# MEGA2560_Rev3e.net
KiCad netlist of a schematic drawn in EAGLE
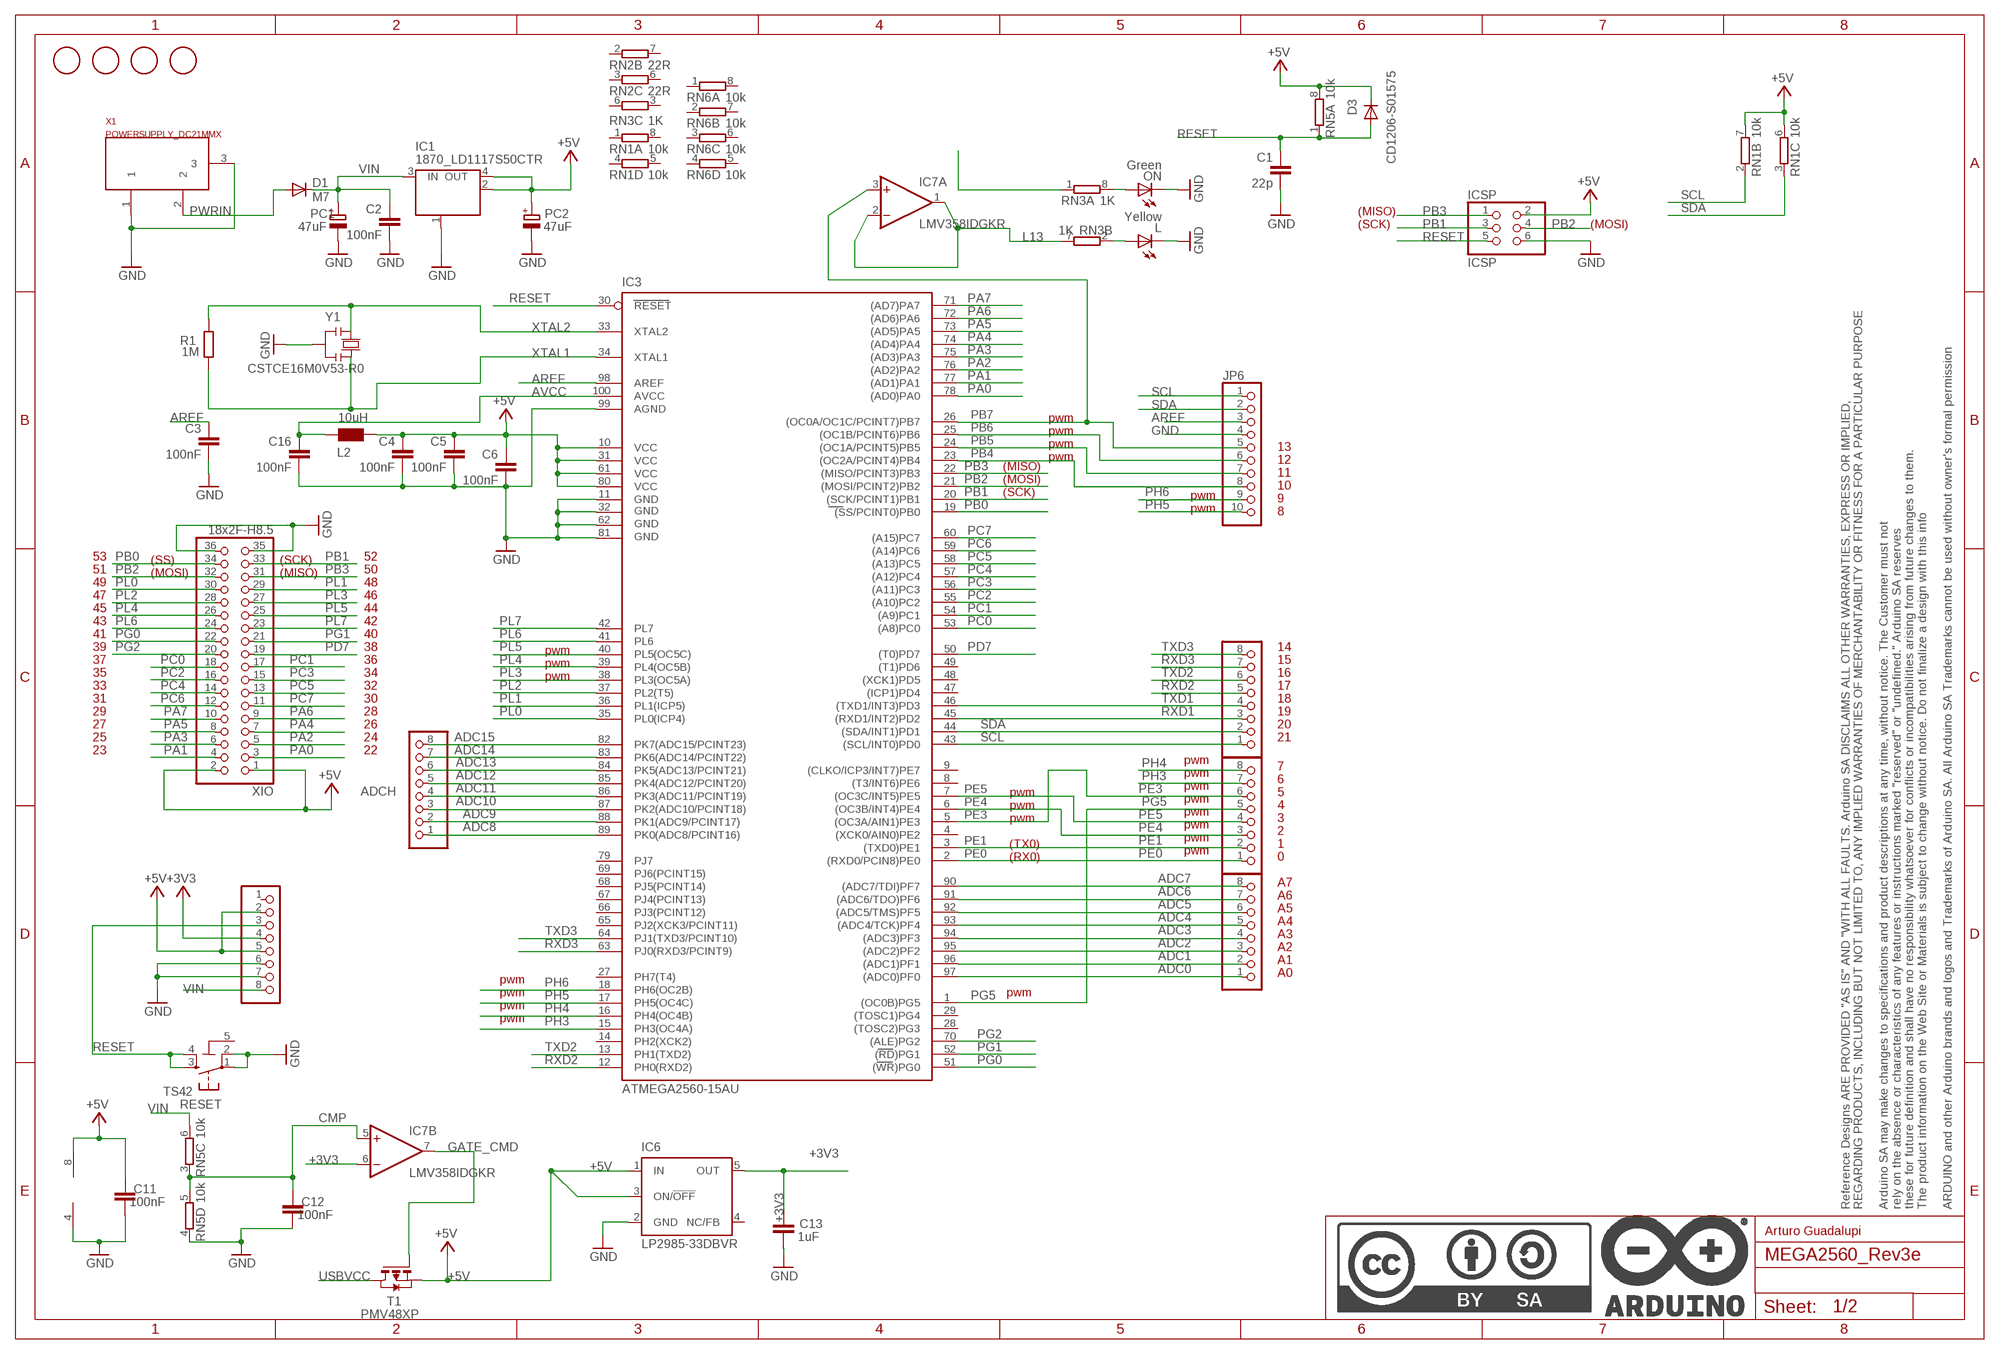
[diagram p0: schematic, sheet 1]
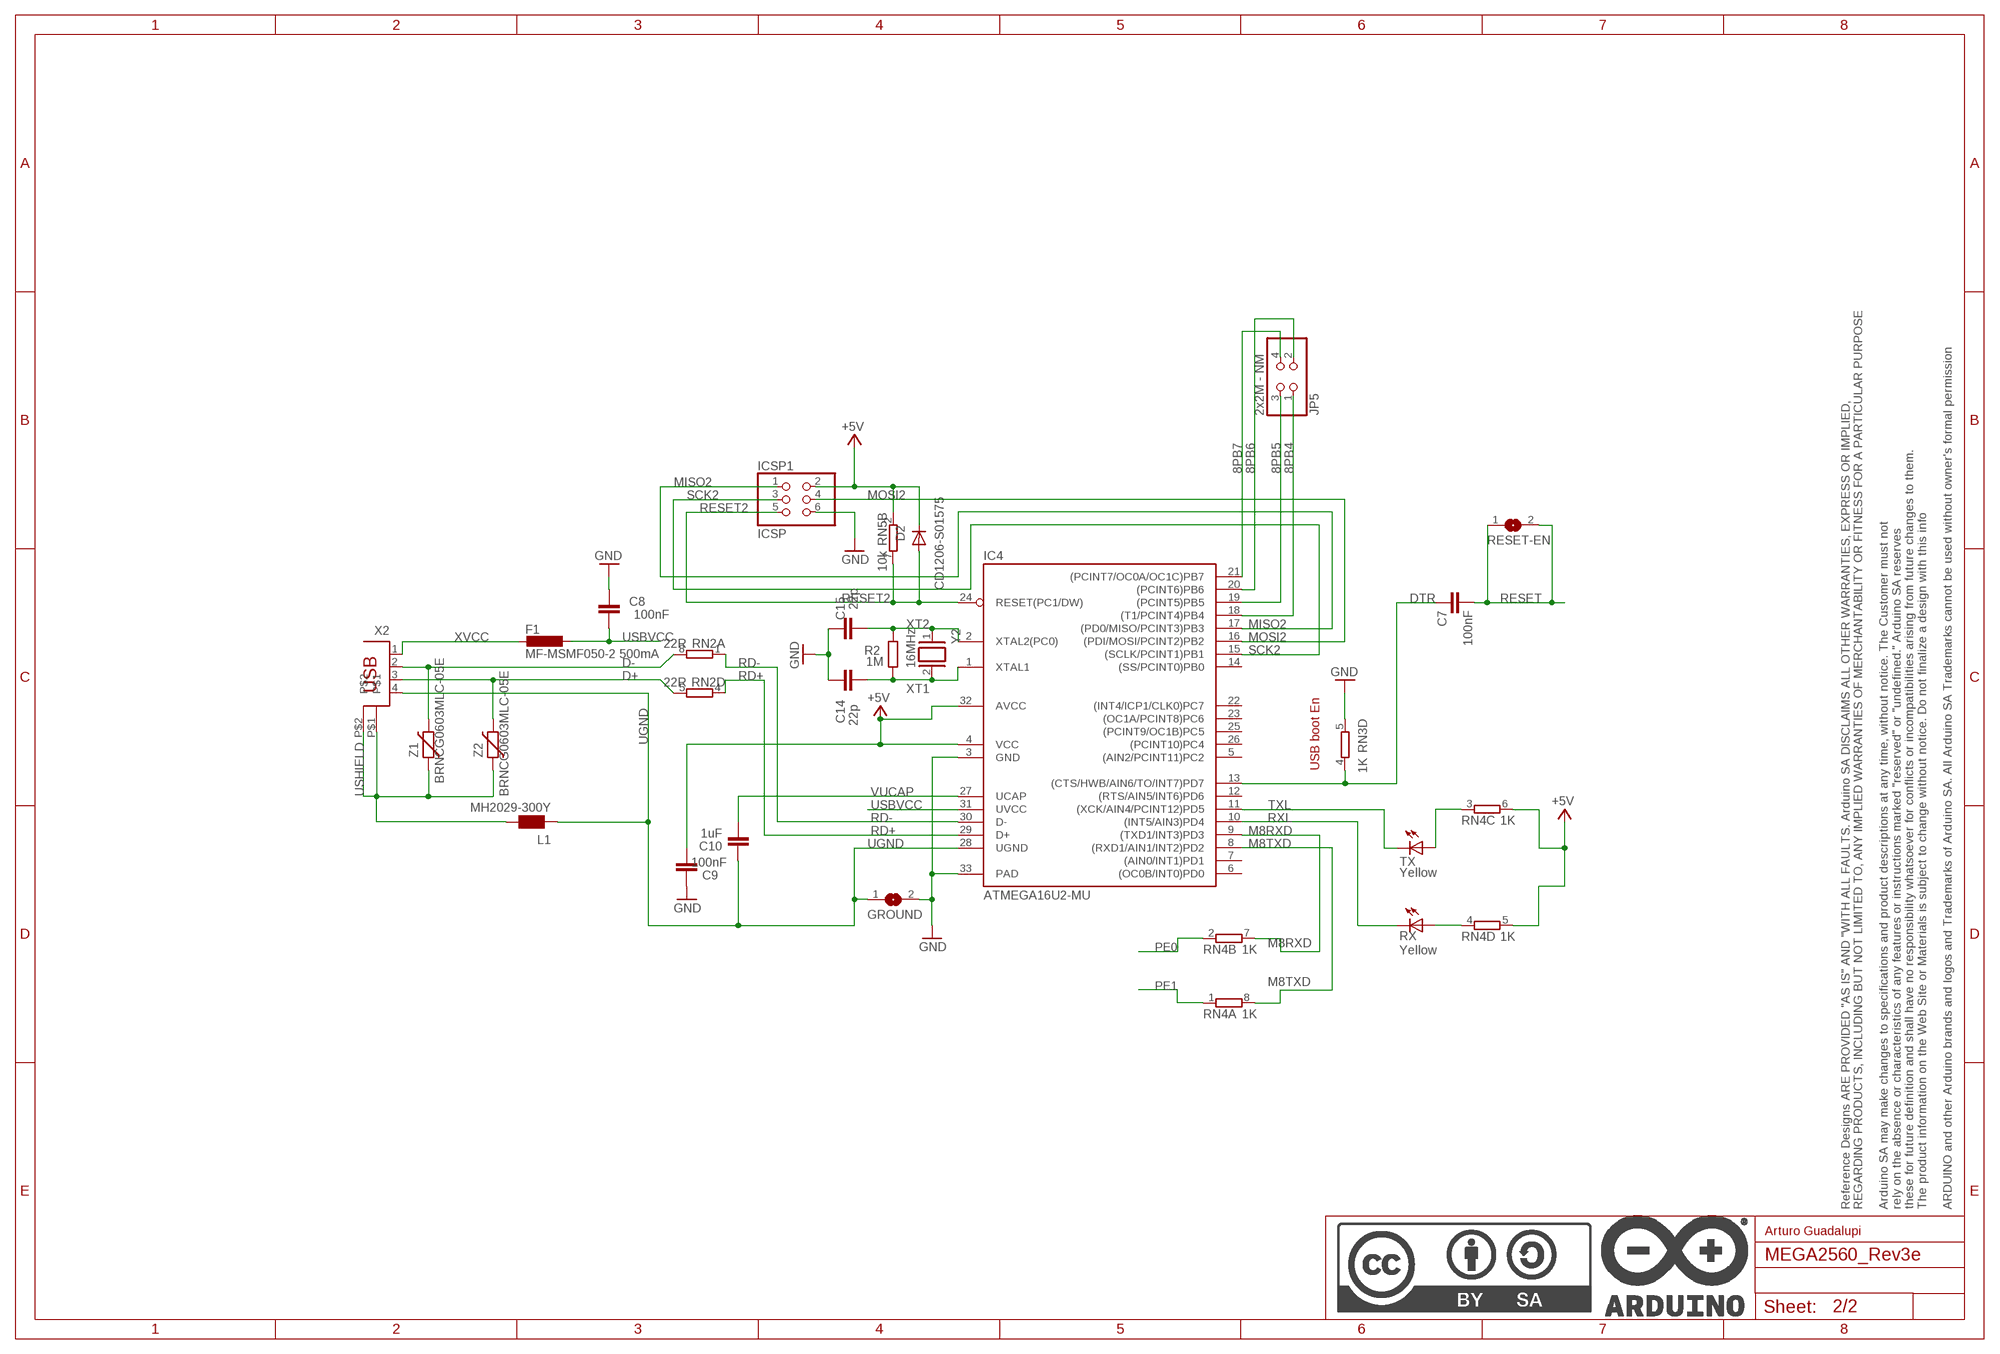
[diagram p1: schematic, sheet 2]

(export (version "E")
  (design (tool "Eeschema 10.0.6"))
  (components
    (comp (ref "C7")
      (value "100nF")
      (footprint "eagle-import:C0603-ROUND")
      (fields (field (name "PART_NUMBER") "cl10b104kbnc"))
      (libsource (lib "eagle-import") (part "0015_100NF_0603"))
    )
    (comp (ref "C8")
      (value "100nF")
      (footprint "eagle-import:C0603-ROUND")
      (fields (field (name "PART_NUMBER") "cl10b104kbnc"))
      (libsource (lib "eagle-import") (part "0015_100NF_0603"))
    )
    (comp (ref "C9")
      (value "100nF")
      (footprint "eagle-import:C0603-ROUND")
      (fields (field (name "PART_NUMBER") "cl10b104kbnc"))
      (libsource (lib "eagle-import") (part "0015_100NF_0603"))
    )
    (comp (ref "C10")
      (value "1uF")
      (footprint "eagle-import:C0603-ROUND")
      (fields (field (name "PART_NUMBER") "1uF_0603/GRM188R61E105KA12D"))
      (libsource (lib "eagle-import") (part "0006_1UF_0603/GRM188R61E105KA12D"))
    )
    (comp (ref "C14")
      (value "22p")
      (footprint "eagle-import:C0603-ROUND")
      (fields (field (name "PART_NUMBER") "22pF_0603"))
      (libsource (lib "eagle-import") (part "0014_22PF_0603"))
    )
    (comp (ref "C15")
      (value "22p")
      (footprint "eagle-import:C0603-ROUND")
      (fields (field (name "PART_NUMBER") "22pF_0603"))
      (libsource (lib "eagle-import") (part "0014_22PF_0603"))
    )
    (comp (ref "D2")
      (value "CD1206-S01575")
      (footprint "eagle-import:MINIMELF")
      (libsource (lib "eagle-import") (part "0012_CD1206-S01575"))
    )
    (comp (ref "F1")
      (value "MF-MSMF050-2 500mA")
      (footprint "eagle-import:L1812")
      (fields (field (name "PART_NUMBER") "MF-MSMF050-2"))
      (libsource (lib "eagle-import") (part "0002_MF-MSMF050-2"))
    )
    (comp (ref "GROUND")
      (value "SJ")
      (footprint "eagle-import:SJ")
      (libsource (lib "eagle-import") (part "SJ"))
    )
    (comp (ref "IC4")
      (value "ATMEGA16U2-MU")
      (footprint "eagle-import:MLF32")
      (fields (field (name "PART_NUMBER") "ATMEGA16U2-MUR"))
      (libsource (lib "eagle-import") (part "0007_ATMEGA16U2-MUR"))
    )
    (comp (ref "ICSP1")
      (value "ICSP")
      (footprint "eagle-import:2X03")
      (fields (field (name "PART_NUMBER") "PH254-203DF118A00V"))
      (libsource (lib "eagle-import") (part "0114_PH254-203DF118A00V"))
    )
    (comp (ref "JP5")
      (value "2x2M - NM")
      (footprint "eagle-import:2X02")
      (libsource (lib "eagle-import") (part "PINHD-2X2"))
    )
    (comp (ref "L1")
      (value "MH2029-300Y")
      (footprint "eagle-import:0805")
      (fields (field (name "PART_NUMBER") "BLM21PG300SN1D_/_MH2029-300Y"))
      (libsource (lib "eagle-import") (part "0001_BLM21PG300SN1D_/_MH2029-300Y"))
    )
    (comp (ref "R2")
      (value "1M")
      (footprint "eagle-import:R0603-ROUND")
      (fields (field (name "PART_NUMBER") "0603_1M"))
      (libsource (lib "eagle-import") (part "0004_0603_1M"))
    )
    (comp (ref "RESET-EN")
      (value "SJ")
      (footprint "eagle-import:SJ")
      (libsource (lib "eagle-import") (part "SJ"))
    )
    (comp (ref "RN2")
      (value "22R")
      (footprint "eagle-import:CAY16")
      (fields (field (name "PART_NUMBER") "064R_22R_/_CAY16-220J4LF"))
      (libsource (lib "eagle-import") (part "0003_064R_22R_/_CAY16-220J4LF"))
    )
    (comp (ref "RN3")
      (value "1K")
      (footprint "eagle-import:CAY16")
      (fields (field (name "PART_NUMBER") "064R_1K_/_CAY16-102J4LF"))
      (libsource (lib "eagle-import") (part "0005_064R_1K_/_CAY16-102J4LF"))
    )
    (comp (ref "RN4")
      (value "1K")
      (footprint "eagle-import:CAY16")
      (fields (field (name "PART_NUMBER") "064R_1K_/_CAY16-102J4LF"))
      (libsource (lib "eagle-import") (part "0005_064R_1K_/_CAY16-102J4LF"))
    )
    (comp (ref "RN5")
      (value "10k")
      (footprint "eagle-import:CAY16")
      (fields (field (name "PART_NUMBER") "064R_10K_/_CAY16-103J4LF"))
      (libsource (lib "eagle-import") (part "0016_064R_10K_/_CAY16-103J4LF"))
    )
    (comp (ref "RX")
      (value "Yellow")
      (footprint "eagle-import:CHIPLED_0805")
      (fields (field (name "PART_NUMBER") "KPT-2012YC"))
      (libsource (lib "eagle-import") (part "0044_KPT-2012YC"))
    )
    (comp (ref "TX")
      (value "Yellow")
      (footprint "eagle-import:CHIPLED_0805")
      (fields (field (name "PART_NUMBER") "KPT-2012YC"))
      (libsource (lib "eagle-import") (part "0044_KPT-2012YC"))
    )
    (comp (ref "U$2")
      (value "DNP")
      (footprint "eagle-import:FRAME")
      (libsource (lib "eagle-import") (part "A3-FRAME"))
    )
    (comp (ref "X2")
      (value "0056_USB-B-S-RA-WT-SPCC")
      (footprint "eagle-import:PN61729")
      (fields (field (name "PART_NUMBER") "USB-B-S-RA-WT-SPCC"))
      (libsource (lib "eagle-import") (part "0056_USB-B-S-RA-WT-SPCC"))
    )
    (comp (ref "Y2")
      (value "16MHz")
      (footprint "eagle-import:QS")
      (fields (field (name "PART_NUMBER") "P011052006 16M/FTX16M20S"))
      (libsource (lib "eagle-import") (part "0019_P011052006_16M"))
    )
    (comp (ref "Z1")
      (value "BRNCG0603MLC-05E")
      (footprint "eagle-import:CT_CN0603")
      (libsource (lib "eagle-import") (part "0010_BRNCG0603MLC-05E"))
    )
    (comp (ref "Z2")
      (value "BRNCG0603MLC-05E")
      (footprint "eagle-import:CT_CN0603")
      (libsource (lib "eagle-import") (part "0010_BRNCG0603MLC-05E"))
    )
    (comp (ref "ADCH")
      (value "FH254-108DF08500V")
      (footprint "eagle-import:1X08")
      (libsource (lib "eagle-import") (part "0058_FH254-108DF08500V"))
    )
    (comp (ref "ADCL")
      (value "FH254-108DF08500V")
      (footprint "eagle-import:1X08")
      (libsource (lib "eagle-import") (part "0058_FH254-108DF08500V"))
    )
    (comp (ref "C1")
      (value "22p")
      (footprint "eagle-import:C0603-ROUND")
      (fields (field (name "PART_NUMBER") "22pF_0603"))
      (libsource (lib "eagle-import") (part "0014_22PF_0603"))
    )
    (comp (ref "C2")
      (value "100nF")
      (footprint "eagle-import:C0603-ROUND")
      (fields (field (name "PART_NUMBER") "cl10b104kbnc"))
      (libsource (lib "eagle-import") (part "0015_100NF_0603"))
    )
    (comp (ref "C3")
      (value "100nF")
      (footprint "eagle-import:C0603-ROUND")
      (fields (field (name "PART_NUMBER") "cl10b104kbnc"))
      (libsource (lib "eagle-import") (part "0015_100NF_0603"))
    )
    (comp (ref "C4")
      (value "100nF")
      (footprint "eagle-import:C0603-ROUND")
      (fields (field (name "PART_NUMBER") "cl10b104kbnc"))
      (libsource (lib "eagle-import") (part "0015_100NF_0603"))
    )
    (comp (ref "C5")
      (value "100nF")
      (footprint "eagle-import:C0603-ROUND")
      (fields (field (name "PART_NUMBER") "cl10b104kbnc"))
      (libsource (lib "eagle-import") (part "0015_100NF_0603"))
    )
    (comp (ref "C6")
      (value "100nF")
      (footprint "eagle-import:C0603-ROUND")
      (fields (field (name "PART_NUMBER") "cl10b104kbnc"))
      (libsource (lib "eagle-import") (part "0015_100NF_0603"))
    )
    (comp (ref "C11")
      (value "100nF")
      (footprint "eagle-import:C0603-ROUND")
      (fields (field (name "PART_NUMBER") "cl10b104kbnc"))
      (libsource (lib "eagle-import") (part "0015_100NF_0603"))
    )
    (comp (ref "C12")
      (value "100nF")
      (footprint "eagle-import:C0603-ROUND")
      (fields (field (name "PART_NUMBER") "cl10b104kbnc"))
      (libsource (lib "eagle-import") (part "0015_100NF_0603"))
    )
    (comp (ref "C13")
      (value "1uF")
      (footprint "eagle-import:C0603-ROUND")
      (fields (field (name "PART_NUMBER") "1uF_0603/GRM188R61E105KA12D"))
      (libsource (lib "eagle-import") (part "0006_1UF_0603/GRM188R61E105KA12D"))
    )
    (comp (ref "C16")
      (value "100nF")
      (footprint "eagle-import:C0603-ROUND")
      (fields (field (name "PART_NUMBER") "cl10b104kbnc"))
      (libsource (lib "eagle-import") (part "0015_100NF_0603"))
    )
    (comp (ref "COMMUNICATION")
      (value "FH254-108DF08500V")
      (footprint "eagle-import:1X08")
      (libsource (lib "eagle-import") (part "0058_FH254-108DF08500V"))
    )
    (comp (ref "D1")
      (value "M7")
      (footprint "eagle-import:SMB")
      (libsource (lib "eagle-import") (part "0020_M7"))
    )
    (comp (ref "D3")
      (value "CD1206-S01575")
      (footprint "eagle-import:MINIMELF")
      (libsource (lib "eagle-import") (part "0012_CD1206-S01575"))
    )
    (comp (ref "FD1")
      (value "FIDUCIALMOUNT")
      (footprint "eagle-import:FIDUCIA-MOUNT")
      (libsource (lib "eagle-import") (part "FIDUCIALMOUNT"))
    )
    (comp (ref "FD2")
      (value "FIDUCIALMOUNT")
      (footprint "eagle-import:FIDUCIA-MOUNT")
      (libsource (lib "eagle-import") (part "FIDUCIALMOUNT"))
    )
    (comp (ref "FD3")
      (value "FIDUCIALMOUNT")
      (footprint "eagle-import:FIDUCIA-MOUNT")
      (libsource (lib "eagle-import") (part "FIDUCIALMOUNT"))
    )
    (comp (ref "FD4")
      (value "FIDUCIALMOUNT")
      (footprint "eagle-import:FIDUCIA-MOUNT")
      (libsource (lib "eagle-import") (part "FIDUCIALMOUNT"))
    )
    (comp (ref "IC1")
      (value "1870_LD1117S50CTR")
      (footprint "eagle-import:LINEAR_SOT223")
      (fields (field (name "PART_NUMBER") "LD1117S50CTR"))
      (libsource (lib "eagle-import") (part "1870_LD1117S50CTR"))
    )
    (comp (ref "IC3")
      (value "ATMEGA2560-15AU")
      (footprint "eagle-import:TQFP100")
      (fields (field (name "PART_NUMBER") "ATMEGA2560-16AU"))
      (libsource (lib "eagle-import") (part "0023_ATMEGA2560-16AU"))
    )
    (comp (ref "IC6")
      (value "LP2985-33DBVR")
      (footprint "eagle-import:SOT23-DBV")
      (fields (field (name "PART_NUMBER") "TEXLP2985-33DBVR"))
      (libsource (lib "eagle-import") (part "0008_TEXLP2985-33DBVR"))
    )
    (comp (ref "IC7")
      (value "LMV358IDGKR")
      (footprint "eagle-import:MSOP08")
      (libsource (lib "eagle-import") (part "0021_LMV358IDGKR"))
    )
    (comp (ref "ICSP")
      (value "ICSP")
      (footprint "eagle-import:2X03")
      (fields (field (name "PART_NUMBER") "PH254-203DF118A00V"))
      (libsource (lib "eagle-import") (part "0114_PH254-203DF118A00V"))
    )
    (comp (ref "JP6")
      (value "FH254-110DF08500V")
      (footprint "eagle-import:1X10")
      (fields (field (name "PART_NUMBER") "FH254-110DF08500T30"))
      (libsource (lib "eagle-import") (part "1216_FH254-110DF08500T30"))
    )
    (comp (ref "L")
      (value "Yellow")
      (footprint "eagle-import:CHIPLED_0805")
      (fields (field (name "PART_NUMBER") "KPT-2012YC"))
      (libsource (lib "eagle-import") (part "0044_KPT-2012YC"))
    )
    (comp (ref "L2")
      (value "10uH")
      (footprint "eagle-import:0805")
      (fields (field (name "PART_NUMBER") "CV201210-100K"))
      (libsource (lib "eagle-import") (part "0715_CV201210-100K"))
    )
    (comp (ref "ON")
      (value "Green")
      (footprint "eagle-import:CHIPLED_0805")
      (fields (field (name "PART_NUMBER") "KPT-2012SGC"))
      (libsource (lib "eagle-import") (part "0043_KPT-2012SGC"))
    )
    (comp (ref "PC1")
      (value "47uF")
      (footprint "eagle-import:PANASONIC_D")
      (libsource (lib "eagle-import") (part "0113_47UF"))
    )
    (comp (ref "PC2")
      (value "47uF")
      (footprint "eagle-import:PANASONIC_D")
      (libsource (lib "eagle-import") (part "0113_47UF"))
    )
    (comp (ref "POWER")
      (value "FH254-108DF08500V")
      (footprint "eagle-import:1X08")
      (fields (field (name "PART_NUMBER") "FH254-108DF08500T21"))
      (libsource (lib "eagle-import") (part "1217_FH254-108DF08500T21"))
    )
    (comp (ref "PWML")
      (value "FH254-108DF08500V")
      (footprint "eagle-import:1X08")
      (fields (field (name "PART_NUMBER") "FH254-108DF08500T20"))
      (libsource (lib "eagle-import") (part "1218_FH254-108DF08500T20"))
    )
    (comp (ref "R1")
      (value "1M")
      (footprint "eagle-import:R0603-ROUND")
      (fields (field (name "PART_NUMBER") "0603_1M"))
      (libsource (lib "eagle-import") (part "0004_0603_1M"))
    )
    (comp (ref "RESET")
      (value "TS42")
      (footprint "eagle-import:TS42")
      (fields (field (name "PART_NUMBER") "IT-1157AHNP-160G-G_GTR"))
      (libsource (lib "eagle-import") (part "0946_TS42031-160W-TR-7260"))
    )
    (comp (ref "RN1")
      (value "10k")
      (footprint "eagle-import:CAY16")
      (fields (field (name "PART_NUMBER") "064R_10K_/_CAY16-103J4LF"))
      (libsource (lib "eagle-import") (part "0016_064R_10K_/_CAY16-103J4LF"))
    )
    (comp (ref "RN6")
      (value "10k")
      (footprint "eagle-import:CAY16")
      (fields (field (name "PART_NUMBER") "064R_10K_/_CAY16-103J4LF"))
      (libsource (lib "eagle-import") (part "0016_064R_10K_/_CAY16-103J4LF"))
    )
    (comp (ref "T1")
      (value "PMV48XP")
      (footprint "eagle-import:SOT-23")
      (fields (field (name "CASE") "SOT23") (field (name "PART_NUMBER") "PMV48XP"))
      (libsource (lib "eagle-import") (part "0297_PMV48XP"))
    )
    (comp (ref "U$1")
      (value "DNP")
      (footprint "eagle-import:FRAME")
      (libsource (lib "eagle-import") (part "A3-FRAME"))
    )
    (comp (ref "X1")
      (value "POWERSUPPLY_DC21MMX")
      (footprint "eagle-import:POWERSUPPLY_DC-21MM")
      (libsource (lib "eagle-import") (part "POWERSUPPLY_DC21MMX"))
    )
    (comp (ref "XIO")
      (value "18x2F-H8.5")
      (footprint "eagle-import:2X18")
      (fields (field (name "PART_NUMBER") "FH254-218DF08500V"))
      (libsource (lib "eagle-import") (part "0060_FH254-218DF08500V"))
    )
    (comp (ref "Y1")
      (value "CSTCE16M0V53-R0")
      (footprint "eagle-import:RESONATOR")
      (libsource (lib "eagle-import") (part "0011_CSTCE16M0V53-R0"))
    )
  )
  (nets
    (net (code "1") (name "+3V3") (class "Default")
      (node (ref "C13") (pin "2") (pinfunction "2_2") (pintype "passive"))
      (node (ref "IC6") (pin "5") (pinfunction "OUT_5") (pintype "passive"))
      (node (ref "IC7") (pin "6") (pinfunction "-IN_6") (pintype "input"))
      (node (ref "POWER") (pin "4") (pinfunction "4_4") (pintype "passive"))
    )
    (net (code "2") (name "+5V") (class "Default")
      (node (ref "C11") (pin "2") (pinfunction "2_2") (pintype "passive"))
      (node (ref "C4") (pin "1") (pinfunction "1_1") (pintype "passive"))
      (node (ref "C5") (pin "1") (pinfunction "1_1") (pintype "passive"))
      (node (ref "C6") (pin "1") (pinfunction "1_1") (pintype "passive"))
      (node (ref "C9") (pin "1") (pinfunction "1_1") (pintype "passive"))
      (node (ref "D2") (pin "C") (pinfunction "C_C") (pintype "passive"))
      (node (ref "D3") (pin "C") (pinfunction "C_C") (pintype "passive"))
      (node (ref "IC1") (pin "2") (pinfunction "OUT_2") (pintype "passive"))
      (node (ref "IC1") (pin "4") (pinfunction "OUT_4") (pintype "passive"))
      (node (ref "IC3") (pin "10") (pinfunction "VCC_10") (pintype "power_in"))
      (node (ref "IC3") (pin "31") (pinfunction "VCC1_31") (pintype "power_in"))
      (node (ref "IC3") (pin "61") (pinfunction "VCC2_61") (pintype "power_in"))
      (node (ref "IC3") (pin "80") (pinfunction "VCC3_80") (pintype "power_in"))
      (node (ref "IC4") (pin "32") (pinfunction "AVCC_32") (pintype "power_in"))
      (node (ref "IC4") (pin "4") (pinfunction "VCC_4") (pintype "power_in"))
      (node (ref "IC6") (pin "1") (pinfunction "IN_1") (pintype "input"))
      (node (ref "IC6") (pin "3") (pinfunction "ON/~{OFF}_3") (pintype "input"))
      (node (ref "IC7") (pin "8") (pinfunction "V+_8") (pintype "power_in"))
      (node (ref "ICSP") (pin "2") (pinfunction "2_2") (pintype "passive"))
      (node (ref "ICSP1") (pin "2") (pinfunction "2_2") (pintype "passive"))
      (node (ref "L2") (pin "2") (pinfunction "2_2") (pintype "passive"))
      (node (ref "PC2") (pin "+") (pinfunction "+_+") (pintype "passive"))
      (node (ref "POWER") (pin "2") (pinfunction "2_2") (pintype "passive"))
      (node (ref "POWER") (pin "5") (pinfunction "5_5") (pintype "passive"))
      (node (ref "RN1") (pin "6") (pinfunction "2_6") (pintype "passive"))
      (node (ref "RN1") (pin "7") (pinfunction "2_7") (pintype "passive"))
      (node (ref "RN4") (pin "5") (pinfunction "2_5") (pintype "passive"))
      (node (ref "RN4") (pin "6") (pinfunction "2_6") (pintype "passive"))
      (node (ref "RN5") (pin "2") (pinfunction "1_2") (pintype "passive"))
      (node (ref "RN5") (pin "8") (pinfunction "2_8") (pintype "passive"))
      (node (ref "T1") (pin "2") (pinfunction "S_2") (pintype "passive"))
      (node (ref "XIO") (pin "1") (pinfunction "1_1") (pintype "passive"))
      (node (ref "XIO") (pin "2") (pinfunction "2_2") (pintype "passive"))
    )
    (net (code "3") (name "5-GND") (class "Default")
      (node (ref "RESET") (pin "5") (pinfunction "5-GND_5") (pintype "power_in"))
    )
    (net (code "4") (name "8PB4") (class "Default")
      (node (ref "IC4") (pin "18") (pinfunction "(T1/PCINT4)PB4_18") (pintype "bidirectional"))
      (node (ref "JP5") (pin "1") (pinfunction "1_1") (pintype "passive"))
    )
    (net (code "5") (name "8PB5") (class "Default")
      (node (ref "IC4") (pin "19") (pinfunction "(PCINT5)PB5_19") (pintype "bidirectional"))
      (node (ref "JP5") (pin "3") (pinfunction "3_3") (pintype "passive"))
    )
    (net (code "6") (name "8PB6") (class "Default")
      (node (ref "IC4") (pin "20") (pinfunction "(PCINT6)PB6_20") (pintype "bidirectional"))
      (node (ref "JP5") (pin "2") (pinfunction "2_2") (pintype "passive"))
    )
    (net (code "7") (name "8PB7") (class "Default")
      (node (ref "IC4") (pin "21") (pinfunction "(PCINT7/OC0A/OC1C)PB7_21") (pintype "bidirectional"))
      (node (ref "JP5") (pin "4") (pinfunction "4_4") (pintype "passive"))
    )
    (net (code "8") (name "ADC0") (class "Default")
      (node (ref "ADCL") (pin "1") (pinfunction "1_1") (pintype "passive"))
      (node (ref "IC3") (pin "97") (pinfunction "(ADC0)PF0_97") (pintype "bidirectional"))
    )
    (net (code "9") (name "ADC1") (class "Default")
      (node (ref "ADCL") (pin "2") (pinfunction "2_2") (pintype "passive"))
      (node (ref "IC3") (pin "96") (pinfunction "(ADC1)PF1_96") (pintype "bidirectional"))
    )
    (net (code "10") (name "ADC2") (class "Default")
      (node (ref "ADCL") (pin "3") (pinfunction "3_3") (pintype "passive"))
      (node (ref "IC3") (pin "95") (pinfunction "(ADC2)PF2_95") (pintype "bidirectional"))
    )
    (net (code "11") (name "ADC3") (class "Default")
      (node (ref "ADCL") (pin "4") (pinfunction "4_4") (pintype "passive"))
      (node (ref "IC3") (pin "94") (pinfunction "(ADC3)PF3_94") (pintype "bidirectional"))
    )
    (net (code "12") (name "ADC4") (class "Default")
      (node (ref "ADCL") (pin "5") (pinfunction "5_5") (pintype "passive"))
      (node (ref "IC3") (pin "93") (pinfunction "(ADC4/TCK)PF4_93") (pintype "bidirectional"))
    )
    (net (code "13") (name "ADC5") (class "Default")
      (node (ref "ADCL") (pin "6") (pinfunction "6_6") (pintype "passive"))
      (node (ref "IC3") (pin "92") (pinfunction "(ADC5/TMS)PF5_92") (pintype "bidirectional"))
    )
    (net (code "14") (name "ADC6") (class "Default")
      (node (ref "ADCL") (pin "7") (pinfunction "7_7") (pintype "passive"))
      (node (ref "IC3") (pin "91") (pinfunction "(ADC6/TDO)PF6_91") (pintype "bidirectional"))
    )
    (net (code "15") (name "ADC7") (class "Default")
      (node (ref "ADCL") (pin "8") (pinfunction "8_8") (pintype "passive"))
      (node (ref "IC3") (pin "90") (pinfunction "(ADC7/TDI)PF7_90") (pintype "bidirectional"))
    )
    (net (code "16") (name "ADC8") (class "Default")
      (node (ref "ADCH") (pin "1") (pinfunction "1_1") (pintype "passive"))
      (node (ref "IC3") (pin "89") (pinfunction "PK0(ADC8/PCINT16)_89") (pintype "bidirectional"))
    )
    (net (code "17") (name "ADC9") (class "Default")
      (node (ref "ADCH") (pin "2") (pinfunction "2_2") (pintype "passive"))
      (node (ref "IC3") (pin "88") (pinfunction "PK1(ADC9/PCINT17)_88") (pintype "bidirectional"))
    )
    (net (code "18") (name "ADC10") (class "Default")
      (node (ref "ADCH") (pin "3") (pinfunction "3_3") (pintype "passive"))
      (node (ref "IC3") (pin "87") (pinfunction "PK2(ADC10/PCINT18)_87") (pintype "bidirectional"))
    )
    (net (code "19") (name "ADC11") (class "Default")
      (node (ref "ADCH") (pin "4") (pinfunction "4_4") (pintype "passive"))
      (node (ref "IC3") (pin "86") (pinfunction "PK3(ADC11/PCINT19)_86") (pintype "bidirectional"))
    )
    (net (code "20") (name "ADC12") (class "Default")
      (node (ref "ADCH") (pin "5") (pinfunction "5_5") (pintype "passive"))
      (node (ref "IC3") (pin "85") (pinfunction "PK4(ADC12/PCINT20)_85") (pintype "bidirectional"))
    )
    (net (code "21") (name "ADC13") (class "Default")
      (node (ref "ADCH") (pin "6") (pinfunction "6_6") (pintype "passive"))
      (node (ref "IC3") (pin "84") (pinfunction "PK5(ADC13/PCINT21)_84") (pintype "bidirectional"))
    )
    (net (code "22") (name "ADC14") (class "Default")
      (node (ref "ADCH") (pin "7") (pinfunction "7_7") (pintype "passive"))
      (node (ref "IC3") (pin "83") (pinfunction "PK6(ADC14/PCINT22)_83") (pintype "bidirectional"))
    )
    (net (code "23") (name "ADC15") (class "Default")
      (node (ref "ADCH") (pin "8") (pinfunction "8_8") (pintype "passive"))
      (node (ref "IC3") (pin "82") (pinfunction "PK7(ADC15/PCINT23)_82") (pintype "bidirectional"))
    )
    (net (code "24") (name "AREF") (class "Default")
      (node (ref "C3") (pin "1") (pinfunction "1_1") (pintype "passive"))
      (node (ref "IC3") (pin "98") (pinfunction "AREF_98") (pintype "bidirectional"))
      (node (ref "JP6") (pin "3") (pinfunction "3_3") (pintype "passive"))
    )
    (net (code "25") (name "AVCC") (class "Default")
      (node (ref "C16") (pin "1") (pinfunction "1_1") (pintype "passive"))
      (node (ref "IC3") (pin "100") (pinfunction "AVCC_100") (pintype "power_in"))
      (node (ref "L2") (pin "1") (pinfunction "1_1") (pintype "passive"))
    )
    (net (code "26") (name "CMP") (class "Default")
      (node (ref "C12") (pin "2") (pinfunction "2_2") (pintype "passive"))
      (node (ref "IC7") (pin "5") (pinfunction "+IN_5") (pintype "input"))
      (node (ref "RN5") (pin "3") (pinfunction "1_3") (pintype "passive"))
      (node (ref "RN5") (pin "5") (pinfunction "2_5") (pintype "passive"))
    )
    (net (code "27") (name "D+") (class "Default")
      (node (ref "RN2") (pin "5") (pinfunction "2_5") (pintype "passive"))
      (node (ref "X2") (pin "3") (pinfunction "3_3") (pintype "bidirectional"))
      (node (ref "Z2") (pin "2") (pinfunction "2_2") (pintype "passive"))
    )
    (net (code "28") (name "D-") (class "Default")
      (node (ref "RN2") (pin "8") (pinfunction "2_8") (pintype "passive"))
      (node (ref "X2") (pin "2") (pinfunction "2_2") (pintype "bidirectional"))
      (node (ref "Z1") (pin "2") (pinfunction "2_2") (pintype "passive"))
    )
    (net (code "29") (name "DTR") (class "Default")
      (node (ref "C7") (pin "1") (pinfunction "1_1") (pintype "passive"))
      (node (ref "IC4") (pin "13") (pinfunction "(CTS/HWB/AIN6/TO/INT7)PD7_13") (pintype "bidirectional"))
      (node (ref "RN3") (pin "4") (pinfunction "1_4") (pintype "passive"))
    )
    (net (code "30") (name "GATE_CMD") (class "Default")
      (node (ref "IC7") (pin "7") (pinfunction "OUT_7") (pintype "output"))
      (node (ref "T1") (pin "3") (pinfunction "G_3") (pintype "passive"))
    )
    (net (code "31") (name "GND") (class "Default")
      (node (ref "C1") (pin "2") (pinfunction "2_2") (pintype "passive"))
      (node (ref "C11") (pin "1") (pinfunction "1_1") (pintype "passive"))
      (node (ref "C12") (pin "1") (pinfunction "1_1") (pintype "passive"))
      (node (ref "C13") (pin "1") (pinfunction "1_1") (pintype "passive"))
      (node (ref "C14") (pin "2") (pinfunction "2_2") (pintype "passive"))
      (node (ref "C15") (pin "2") (pinfunction "2_2") (pintype "passive"))
      (node (ref "C16") (pin "2") (pinfunction "2_2") (pintype "passive"))
      (node (ref "C2") (pin "2") (pinfunction "2_2") (pintype "passive"))
      (node (ref "C3") (pin "2") (pinfunction "2_2") (pintype "passive"))
      (node (ref "C4") (pin "2") (pinfunction "2_2") (pintype "passive"))
      (node (ref "C5") (pin "2") (pinfunction "2_2") (pintype "passive"))
      (node (ref "C6") (pin "2") (pinfunction "2_2") (pintype "passive"))
      (node (ref "C8") (pin "2") (pinfunction "2_2") (pintype "passive"))
      (node (ref "C9") (pin "2") (pinfunction "2_2") (pintype "passive"))
      (node (ref "GROUND") (pin "2") (pinfunction "2_2") (pintype "passive"))
      (node (ref "IC1") (pin "1") (pinfunction "GND/ADJ_1") (pintype "input"))
      (node (ref "IC3") (pin "11") (pinfunction "GND_11") (pintype "power_in"))
      (node (ref "IC3") (pin "32") (pinfunction "GND1_32") (pintype "power_in"))
      (node (ref "IC3") (pin "62") (pinfunction "GND2_62") (pintype "power_in"))
      (node (ref "IC3") (pin "81") (pinfunction "GND3_81") (pintype "power_in"))
      (node (ref "IC3") (pin "99") (pinfunction "AGND_99") (pintype "power_in"))
      (node (ref "IC4") (pin "3") (pinfunction "GND_3") (pintype "power_in"))
      (node (ref "IC4") (pin "33") (pinfunction "PAD_33") (pintype "power_in"))
      (node (ref "IC6") (pin "2") (pinfunction "GND_2") (pintype "power_in"))
      (node (ref "IC7") (pin "4") (pinfunction "V-_4") (pintype "power_in"))
      (node (ref "ICSP") (pin "6") (pinfunction "6_6") (pintype "passive"))
      (node (ref "ICSP1") (pin "6") (pinfunction "6_6") (pintype "passive"))
      (node (ref "JP6") (pin "4") (pinfunction "4_4") (pintype "passive"))
      (node (ref "L") (pin "C") (pinfunction "C_C") (pintype "passive"))
      (node (ref "ON") (pin "C") (pinfunction "C_C") (pintype "passive"))
      (node (ref "PC1") (pin "-") (pinfunction "-_-") (pintype "passive"))
      (node (ref "PC2") (pin "-") (pinfunction "-_-") (pintype "passive"))
      (node (ref "POWER") (pin "6") (pinfunction "6_6") (pintype "passive"))
      (node (ref "POWER") (pin "7") (pinfunction "7_7") (pintype "passive"))
      (node (ref "RESET") (pin "1") (pinfunction "1_1") (pintype "passive"))
      (node (ref "RESET") (pin "2") (pinfunction "2_2") (pintype "passive"))
      (node (ref "RN3") (pin "5") (pinfunction "2_5") (pintype "passive"))
      (node (ref "RN5") (pin "4") (pinfunction "1_4") (pintype "passive"))
      (node (ref "X1") (pin "1") (pinfunction "1_1") (pintype "power_in"))
      (node (ref "X1") (pin "3") (pinfunction "3_3") (pintype "power_in"))
      (node (ref "XIO") (pin "35") (pinfunction "35_35") (pintype "passive"))
      (node (ref "XIO") (pin "36") (pinfunction "36_36") (pintype "passive"))
      (node (ref "Y1") (pin "2") (pinfunction "2_2") (pintype "passive"))
    )
    (net (code "32") (name "L13") (class "Default")
      (node (ref "IC7") (pin "1") (pinfunction "OUT_1") (pintype "output"))
      (node (ref "IC7") (pin "2") (pinfunction "-IN_2") (pintype "input"))
      (node (ref "RN3") (pin "7") (pinfunction "2_7") (pintype "passive"))
    )
    (net (code "33") (name "M8RXD") (class "Default")
      (node (ref "IC4") (pin "9") (pinfunction "(TXD1/INT3)PD3_9") (pintype "bidirectional"))
      (node (ref "RN4") (pin "7") (pinfunction "2_7") (pintype "passive"))
    )
    (net (code "34") (name "M8TXD") (class "Default")
      (node (ref "IC4") (pin "8") (pinfunction "(RXD1/AIN1/INT2)PD2_8") (pintype "bidirectional"))
      (node (ref "RN4") (pin "8") (pinfunction "2_8") (pintype "passive"))
    )
    (net (code "35") (name "MISO2") (class "Default")
      (node (ref "IC4") (pin "17") (pinfunction "(PD0/MISO/PCINT3)PB3_17") (pintype "bidirectional"))
      (node (ref "ICSP1") (pin "1") (pinfunction "1_1") (pintype "passive"))
    )
    (net (code "36") (name "MOSI2") (class "Default")
      (node (ref "IC4") (pin "16") (pinfunction "(PDI/MOSI/PCINT2)PB2_16") (pintype "bidirectional"))
      (node (ref "ICSP1") (pin "4") (pinfunction "4_4") (pintype "passive"))
    )
    (net (code "37") (name "Net-(RN3A-2)") (class "Default")
      (node (ref "ON") (pin "A") (pinfunction "A_A") (pintype "passive"))
      (node (ref "RN3") (pin "8") (pinfunction "2_8") (pintype "passive"))
    )
    (net (code "38") (name "Net-(RN3B-1)") (class "Default")
      (node (ref "L") (pin "A") (pinfunction "A_A") (pintype "passive"))
      (node (ref "RN3") (pin "2") (pinfunction "1_2") (pintype "passive"))
    )
    (net (code "39") (name "Net-(RN4C-1)") (class "Default")
      (node (ref "RN4") (pin "3") (pinfunction "1_3") (pintype "passive"))
      (node (ref "TX") (pin "A") (pinfunction "A_A") (pintype "passive"))
    )
    (net (code "40") (name "Net-(RN4D-1)") (class "Default")
      (node (ref "RN4") (pin "4") (pinfunction "1_4") (pintype "passive"))
      (node (ref "RX") (pin "A") (pinfunction "A_A") (pintype "passive"))
    )
    (net (code "41") (name "PA0") (class "Default")
      (node (ref "IC3") (pin "78") (pinfunction "(AD0)PA0_78") (pintype "bidirectional"))
      (node (ref "XIO") (pin "3") (pinfunction "3_3") (pintype "passive"))
    )
    (net (code "42") (name "PA1") (class "Default")
      (node (ref "IC3") (pin "77") (pinfunction "(AD1)PA1_77") (pintype "bidirectional"))
      (node (ref "XIO") (pin "4") (pinfunction "4_4") (pintype "passive"))
    )
    (net (code "43") (name "PA2") (class "Default")
      (node (ref "IC3") (pin "76") (pinfunction "(AD2)PA2_76") (pintype "bidirectional"))
      (node (ref "XIO") (pin "5") (pinfunction "5_5") (pintype "passive"))
    )
    (net (code "44") (name "PA3") (class "Default")
      (node (ref "IC3") (pin "75") (pinfunction "(AD3)PA3_75") (pintype "bidirectional"))
      (node (ref "XIO") (pin "6") (pinfunction "6_6") (pintype "passive"))
    )
    (net (code "45") (name "PA4") (class "Default")
      (node (ref "IC3") (pin "74") (pinfunction "(AD4)PA4_74") (pintype "bidirectional"))
      (node (ref "XIO") (pin "7") (pinfunction "7_7") (pintype "passive"))
    )
    (net (code "46") (name "PA5") (class "Default")
      (node (ref "IC3") (pin "73") (pinfunction "(AD5)PA5_73") (pintype "bidirectional"))
      (node (ref "XIO") (pin "8") (pinfunction "8_8") (pintype "passive"))
    )
    (net (code "47") (name "PA6") (class "Default")
      (node (ref "IC3") (pin "72") (pinfunction "(AD6)PA6_72") (pintype "bidirectional"))
      (node (ref "XIO") (pin "9") (pinfunction "9_9") (pintype "passive"))
    )
    (net (code "48") (name "PA7") (class "Default")
      (node (ref "IC3") (pin "71") (pinfunction "(AD7)PA7_71") (pintype "bidirectional"))
      (node (ref "XIO") (pin "10") (pinfunction "10_10") (pintype "passive"))
    )
    (net (code "49") (name "PB0") (class "Default")
      (node (ref "IC3") (pin "19") (pinfunction "(SS/PCINT0)PB0_19") (pintype "bidirectional"))
      (node (ref "XIO") (pin "34") (pinfunction "34_34") (pintype "passive"))
    )
    (net (code "50") (name "PB1") (class "Default")
      (node (ref "IC3") (pin "20") (pinfunction "(SCK/PCINT1)PB1_20") (pintype "bidirectional"))
      (node (ref "ICSP") (pin "3") (pinfunction "3_3") (pintype "passive"))
      (node (ref "XIO") (pin "33") (pinfunction "33_33") (pintype "passive"))
    )
    (net (code "51") (name "PB2") (class "Default")
      (node (ref "IC3") (pin "21") (pinfunction "(MOSI/PCINT2)PB2_21") (pintype "bidirectional"))
      (node (ref "ICSP") (pin "4") (pinfunction "4_4") (pintype "passive"))
      (node (ref "XIO") (pin "32") (pinfunction "32_32") (pintype "passive"))
    )
    (net (code "52") (name "PB3") (class "Default")
      (node (ref "IC3") (pin "22") (pinfunction "(MISO/PCINT3)PB3_22") (pintype "bidirectional"))
      (node (ref "ICSP") (pin "1") (pinfunction "1_1") (pintype "passive"))
      (node (ref "XIO") (pin "31") (pinfunction "31_31") (pintype "passive"))
    )
    (net (code "53") (name "PB4") (class "Default")
      (node (ref "IC3") (pin "23") (pinfunction "(OC2A/PCINT4)PB4_23") (pintype "bidirectional"))
      (node (ref "JP6") (pin "8") (pinfunction "8_8") (pintype "passive"))
    )
    (net (code "54") (name "PB5") (class "Default")
      (node (ref "IC3") (pin "24") (pinfunction "(OC1A/PCINT5)PB5_24") (pintype "bidirectional"))
      (node (ref "JP6") (pin "7") (pinfunction "7_7") (pintype "passive"))
    )
    (net (code "55") (name "PB6") (class "Default")
      (node (ref "IC3") (pin "25") (pinfunction "(OC1B/PCINT6)PB6_25") (pintype "bidirectional"))
      (node (ref "JP6") (pin "6") (pinfunction "6_6") (pintype "passive"))
    )
    (net (code "56") (name "PB7") (class "Default")
      (node (ref "IC3") (pin "26") (pinfunction "(OC0A/OC1C/PCINT7)PB7_26") (pintype "bidirectional"))
      (node (ref "IC7") (pin "3") (pinfunction "+IN_3") (pintype "input"))
      (node (ref "JP6") (pin "5") (pinfunction "5_5") (pintype "passive"))
    )
    (net (code "57") (name "PC0") (class "Default")
      (node (ref "IC3") (pin "53") (pinfunction "(A8)PC0_53") (pintype "bidirectional"))
      (node (ref "XIO") (pin "18") (pinfunction "18_18") (pintype "passive"))
    )
    (net (code "58") (name "PC1") (class "Default")
      (node (ref "IC3") (pin "54") (pinfunction "(A9)PC1_54") (pintype "bidirectional"))
      (node (ref "XIO") (pin "17") (pinfunction "17_17") (pintype "passive"))
    )
    (net (code "59") (name "PC2") (class "Default")
      (node (ref "IC3") (pin "55") (pinfunction "(A10)PC2_55") (pintype "bidirectional"))
      (node (ref "XIO") (pin "16") (pinfunction "16_16") (pintype "passive"))
    )
    (net (code "60") (name "PC3") (class "Default")
      (node (ref "IC3") (pin "56") (pinfunction "(A11)PC3_56") (pintype "bidirectional"))
      (node (ref "XIO") (pin "15") (pinfunction "15_15") (pintype "passive"))
    )
    (net (code "61") (name "PC4") (class "Default")
      (node (ref "IC3") (pin "57") (pinfunction "(A12)PC4_57") (pintype "bidirectional"))
      (node (ref "XIO") (pin "14") (pinfunction "14_14") (pintype "passive"))
    )
    (net (code "62") (name "PC5") (class "Default")
      (node (ref "IC3") (pin "58") (pinfunction "(A13)PC5_58") (pintype "bidirectional"))
      (node (ref "XIO") (pin "13") (pinfunction "13_13") (pintype "passive"))
    )
    (net (code "63") (name "PC6") (class "Default")
      (node (ref "IC3") (pin "59") (pinfunction "(A14)PC6_59") (pintype "bidirectional"))
      (node (ref "XIO") (pin "12") (pinfunction "12_12") (pintype "passive"))
    )
    (net (code "64") (name "PC7") (class "Default")
      (node (ref "IC3") (pin "60") (pinfunction "(A15)PC7_60") (pintype "bidirectional"))
      (node (ref "XIO") (pin "11") (pinfunction "11_11") (pintype "passive"))
    )
    (net (code "65") (name "PD7") (class "Default")
      (node (ref "IC3") (pin "50") (pinfunction "(T0)PD7_50") (pintype "bidirectional"))
      (node (ref "XIO") (pin "19") (pinfunction "19_19") (pintype "passive"))
    )
    (net (code "66") (name "PE0") (class "Default")
      (node (ref "IC3") (pin "2") (pinfunction "(RXD0/PCIN8)PE0_2") (pintype "bidirectional"))
      (node (ref "PWML") (pin "1") (pinfunction "1_1") (pintype "passive"))
      (node (ref "RN4") (pin "2") (pinfunction "1_2") (pintype "passive"))
    )
    (net (code "67") (name "PE1") (class "Default")
      (node (ref "IC3") (pin "3") (pinfunction "(TXD0)PE1_3") (pintype "bidirectional"))
      (node (ref "PWML") (pin "2") (pinfunction "2_2") (pintype "passive"))
      (node (ref "RN4") (pin "1") (pinfunction "1_1") (pintype "passive"))
    )
    (net (code "68") (name "PE3") (class "Default")
      (node (ref "IC3") (pin "5") (pinfunction "(OC3A/AIN1)PE3_5") (pintype "bidirectional"))
      (node (ref "PWML") (pin "6") (pinfunction "6_6") (pintype "passive"))
    )
    (net (code "69") (name "PE4") (class "Default")
      (node (ref "IC3") (pin "6") (pinfunction "(OC3B/INT4)PE4_6") (pintype "bidirectional"))
      (node (ref "PWML") (pin "3") (pinfunction "3_3") (pintype "passive"))
    )
    (net (code "70") (name "PE5") (class "Default")
      (node (ref "IC3") (pin "7") (pinfunction "(OC3C/INT5)PE5_7") (pintype "bidirectional"))
      (node (ref "PWML") (pin "4") (pinfunction "4_4") (pintype "passive"))
    )
    (net (code "71") (name "PG0") (class "Default")
      (node (ref "IC3") (pin "51") (pinfunction "(WR)PG0_51") (pintype "bidirectional"))
      (node (ref "XIO") (pin "22") (pinfunction "22_22") (pintype "passive"))
    )
    (net (code "72") (name "PG1") (class "Default")
      (node (ref "IC3") (pin "52") (pinfunction "(RD)PG1_52") (pintype "bidirectional"))
      (node (ref "XIO") (pin "21") (pinfunction "21_21") (pintype "passive"))
    )
    (net (code "73") (name "PG2") (class "Default")
      (node (ref "IC3") (pin "70") (pinfunction "(ALE)PG2_70") (pintype "bidirectional"))
      (node (ref "XIO") (pin "20") (pinfunction "20_20") (pintype "passive"))
    )
    (net (code "74") (name "PG5") (class "Default")
      (node (ref "IC3") (pin "1") (pinfunction "(OC0B)PG5_1") (pintype "bidirectional"))
      (node (ref "PWML") (pin "5") (pinfunction "5_5") (pintype "passive"))
    )
    (net (code "75") (name "PH3") (class "Default")
      (node (ref "IC3") (pin "15") (pinfunction "PH3(OC4A)_15") (pintype "bidirectional"))
      (node (ref "PWML") (pin "7") (pinfunction "7_7") (pintype "passive"))
    )
    (net (code "76") (name "PH4") (class "Default")
      (node (ref "IC3") (pin "16") (pinfunction "PH4(OC4B)_16") (pintype "bidirectional"))
      (node (ref "PWML") (pin "8") (pinfunction "8_8") (pintype "passive"))
    )
    (net (code "77") (name "PH5") (class "Default")
      (node (ref "IC3") (pin "17") (pinfunction "PH5(OC4C)_17") (pintype "bidirectional"))
      (node (ref "JP6") (pin "10") (pinfunction "10_10") (pintype "passive"))
    )
    (net (code "78") (name "PH6") (class "Default")
      (node (ref "IC3") (pin "18") (pinfunction "PH6(OC2B)_18") (pintype "bidirectional"))
      (node (ref "JP6") (pin "9") (pinfunction "9_9") (pintype "passive"))
    )
    (net (code "79") (name "PL0") (class "Default")
      (node (ref "IC3") (pin "35") (pinfunction "PL0(ICP4)_35") (pintype "bidirectional"))
      (node (ref "XIO") (pin "30") (pinfunction "30_30") (pintype "passive"))
    )
    (net (code "80") (name "PL1") (class "Default")
      (node (ref "IC3") (pin "36") (pinfunction "PL1(ICP5)_36") (pintype "bidirectional"))
      (node (ref "XIO") (pin "29") (pinfunction "29_29") (pintype "passive"))
    )
    (net (code "81") (name "PL2") (class "Default")
      (node (ref "IC3") (pin "37") (pinfunction "PL2(T5)_37") (pintype "bidirectional"))
      (node (ref "XIO") (pin "28") (pinfunction "28_28") (pintype "passive"))
    )
    (net (code "82") (name "PL3") (class "Default")
      (node (ref "IC3") (pin "38") (pinfunction "PL3(OC5A)_38") (pintype "bidirectional"))
      (node (ref "XIO") (pin "27") (pinfunction "27_27") (pintype "passive"))
    )
    (net (code "83") (name "PL4") (class "Default")
      (node (ref "IC3") (pin "39") (pinfunction "PL4(OC5B)_39") (pintype "bidirectional"))
      (node (ref "XIO") (pin "26") (pinfunction "26_26") (pintype "passive"))
    )
    (net (code "84") (name "PL5") (class "Default")
      (node (ref "IC3") (pin "40") (pinfunction "PL5(OC5C)_40") (pintype "bidirectional"))
      (node (ref "XIO") (pin "25") (pinfunction "25_25") (pintype "passive"))
    )
    (net (code "85") (name "PL6") (class "Default")
      (node (ref "IC3") (pin "41") (pinfunction "PL6_41") (pintype "bidirectional"))
      (node (ref "XIO") (pin "24") (pinfunction "24_24") (pintype "passive"))
    )
    (net (code "86") (name "PL7") (class "Default")
      (node (ref "IC3") (pin "42") (pinfunction "PL7_42") (pintype "bidirectional"))
      (node (ref "XIO") (pin "23") (pinfunction "23_23") (pintype "passive"))
    )
    (net (code "87") (name "PWRIN") (class "Default")
      (node (ref "D1") (pin "A") (pinfunction "A_A") (pintype "passive"))
      (node (ref "X1") (pin "2") (pinfunction "2_2") (pintype "power_in"))
    )
    (net (code "88") (name "RD+") (class "Default")
      (node (ref "IC4") (pin "29") (pinfunction "D+_29") (pintype "bidirectional"))
      (node (ref "RN2") (pin "4") (pinfunction "1_4") (pintype "passive"))
    )
    (net (code "89") (name "RD-") (class "Default")
      (node (ref "IC4") (pin "30") (pinfunction "D-_30") (pintype "bidirectional"))
      (node (ref "RN2") (pin "1") (pinfunction "1_1") (pintype "passive"))
    )
    (net (code "90") (name "RESET") (class "Default")
      (node (ref "C1") (pin "1") (pinfunction "1_1") (pintype "passive"))
      (node (ref "C7") (pin "2") (pinfunction "2_2") (pintype "passive"))
      (node (ref "D3") (pin "A") (pinfunction "A_A") (pintype "passive"))
      (node (ref "IC3") (pin "30") (pinfunction "RESET_30") (pintype "input"))
      (node (ref "ICSP") (pin "5") (pinfunction "5_5") (pintype "passive"))
      (node (ref "POWER") (pin "3") (pinfunction "3_3") (pintype "passive"))
      (node (ref "RESET") (pin "3") (pinfunction "3_3") (pintype "passive"))
      (node (ref "RESET") (pin "4") (pinfunction "4_4") (pintype "passive"))
      (node (ref "RESET-EN") (pin "1") (pinfunction "1_1") (pintype "passive"))
      (node (ref "RESET-EN") (pin "2") (pinfunction "2_2") (pintype "passive"))
      (node (ref "RN5") (pin "1") (pinfunction "1_1") (pintype "passive"))
    )
    (net (code "91") (name "RESET2") (class "Default")
      (node (ref "D2") (pin "A") (pinfunction "A_A") (pintype "passive"))
      (node (ref "IC4") (pin "24") (pinfunction "RESET(PC1/DW)_24") (pintype "input"))
      (node (ref "ICSP1") (pin "5") (pinfunction "5_5") (pintype "passive"))
      (node (ref "RN5") (pin "7") (pinfunction "2_7") (pintype "passive"))
    )
    (net (code "92") (name "RXD1") (class "Default")
      (node (ref "COMMUNICATION") (pin "3") (pinfunction "3_3") (pintype "passive"))
      (node (ref "IC3") (pin "45") (pinfunction "(RXD1/INT2)PD2_45") (pintype "bidirectional"))
    )
    (net (code "93") (name "RXD2") (class "Default")
      (node (ref "COMMUNICATION") (pin "5") (pinfunction "5_5") (pintype "passive"))
      (node (ref "IC3") (pin "12") (pinfunction "PH0(RXD2)_12") (pintype "bidirectional"))
    )
    (net (code "94") (name "RXD3") (class "Default")
      (node (ref "COMMUNICATION") (pin "7") (pinfunction "7_7") (pintype "passive"))
      (node (ref "IC3") (pin "63") (pinfunction "PJ0(RXD3/PCINT9)_63") (pintype "bidirectional"))
    )
    (net (code "95") (name "RXL") (class "Default")
      (node (ref "IC4") (pin "10") (pinfunction "(INT5/AIN3)PD4_10") (pintype "bidirectional"))
      (node (ref "RX") (pin "C") (pinfunction "C_C") (pintype "passive"))
    )
    (net (code "96") (name "SCK2") (class "Default")
      (node (ref "IC4") (pin "15") (pinfunction "(SCLK/PCINT1)PB1_15") (pintype "bidirectional"))
      (node (ref "ICSP1") (pin "3") (pinfunction "3_3") (pintype "passive"))
    )
    (net (code "97") (name "SCL") (class "Default")
      (node (ref "COMMUNICATION") (pin "1") (pinfunction "1_1") (pintype "passive"))
      (node (ref "IC3") (pin "43") (pinfunction "(SCL/INT0)PD0_43") (pintype "bidirectional"))
      (node (ref "JP6") (pin "1") (pinfunction "1_1") (pintype "passive"))
      (node (ref "RN1") (pin "2") (pinfunction "1_2") (pintype "passive"))
    )
    (net (code "98") (name "SDA") (class "Default")
      (node (ref "COMMUNICATION") (pin "2") (pinfunction "2_2") (pintype "passive"))
      (node (ref "IC3") (pin "44") (pinfunction "(SDA/INT1)PD1_44") (pintype "bidirectional"))
      (node (ref "JP6") (pin "2") (pinfunction "2_2") (pintype "passive"))
      (node (ref "RN1") (pin "3") (pinfunction "1_3") (pintype "passive"))
    )
    (net (code "99") (name "TXD1") (class "Default")
      (node (ref "COMMUNICATION") (pin "4") (pinfunction "4_4") (pintype "passive"))
      (node (ref "IC3") (pin "46") (pinfunction "(TXD1/INT3)PD3_46") (pintype "bidirectional"))
    )
    (net (code "100") (name "TXD2") (class "Default")
      (node (ref "COMMUNICATION") (pin "6") (pinfunction "6_6") (pintype "passive"))
      (node (ref "IC3") (pin "13") (pinfunction "PH1(TXD2)_13") (pintype "bidirectional"))
    )
    (net (code "101") (name "TXD3") (class "Default")
      (node (ref "COMMUNICATION") (pin "8") (pinfunction "8_8") (pintype "passive"))
      (node (ref "IC3") (pin "64") (pinfunction "PJ1(TXD3/PCINT10)_64") (pintype "bidirectional"))
    )
    (net (code "102") (name "TXL") (class "Default")
      (node (ref "IC4") (pin "11") (pinfunction "(XCK/AIN4/PCINT12)PD5_11") (pintype "bidirectional"))
      (node (ref "TX") (pin "C") (pinfunction "C_C") (pintype "passive"))
    )
    (net (code "103") (name "UGND") (class "Default")
      (node (ref "C10") (pin "2") (pinfunction "2_2") (pintype "passive"))
      (node (ref "GROUND") (pin "1") (pinfunction "1_1") (pintype "passive"))
      (node (ref "IC4") (pin "28") (pinfunction "UGND_28") (pintype "power_in"))
      (node (ref "L1") (pin "1") (pinfunction "1_1") (pintype "passive"))
      (node (ref "X2") (pin "4") (pinfunction "4_4") (pintype "bidirectional"))
    )
    (net (code "104") (name "USBVCC") (class "Default")
      (node (ref "C8") (pin "1") (pinfunction "1_1") (pintype "passive"))
      (node (ref "F1") (pin "1") (pinfunction "1_1") (pintype "passive"))
      (node (ref "IC4") (pin "31") (pinfunction "UVCC_31") (pintype "power_in"))
      (node (ref "T1") (pin "1") (pinfunction "D_1") (pintype "passive"))
    )
    (net (code "105") (name "USHIELD") (class "Default")
      (node (ref "L1") (pin "2") (pinfunction "2_2") (pintype "passive"))
      (node (ref "X2") (pin "P$1") (pinfunction "P$1_P$1") (pintype "bidirectional"))
      (node (ref "X2") (pin "P$2") (pinfunction "P$2_P$2") (pintype "bidirectional"))
      (node (ref "Z1") (pin "1") (pinfunction "1_1") (pintype "passive"))
      (node (ref "Z2") (pin "1") (pinfunction "1_1") (pintype "passive"))
    )
    (net (code "106") (name "VIN") (class "Default")
      (node (ref "C2") (pin "1") (pinfunction "1_1") (pintype "passive"))
      (node (ref "D1") (pin "C") (pinfunction "C_C") (pintype "passive"))
      (node (ref "IC1") (pin "3") (pinfunction "IN_3") (pintype "input"))
      (node (ref "PC1") (pin "+") (pinfunction "+_+") (pintype "passive"))
      (node (ref "POWER") (pin "8") (pinfunction "8_8") (pintype "passive"))
      (node (ref "RN5") (pin "6") (pinfunction "2_6") (pintype "passive"))
    )
    (net (code "107") (name "VUCAP") (class "Default")
      (node (ref "C10") (pin "1") (pinfunction "1_1") (pintype "passive"))
      (node (ref "IC4") (pin "27") (pinfunction "UCAP_27") (pintype "passive"))
    )
    (net (code "108") (name "XT1") (class "Default")
      (node (ref "C14") (pin "1") (pinfunction "1_1") (pintype "passive"))
      (node (ref "IC4") (pin "1") (pinfunction "XTAL1_1") (pintype "bidirectional"))
      (node (ref "R2") (pin "1") (pinfunction "1_1") (pintype "passive"))
      (node (ref "Y2") (pin "2") (pinfunction "2_2") (pintype "passive"))
    )
    (net (code "109") (name "XT2") (class "Default")
      (node (ref "C15") (pin "1") (pinfunction "1_1") (pintype "passive"))
      (node (ref "IC4") (pin "2") (pinfunction "XTAL2(PC0)_2") (pintype "bidirectional"))
      (node (ref "R2") (pin "2") (pinfunction "2_2") (pintype "passive"))
      (node (ref "Y2") (pin "1") (pinfunction "1_1") (pintype "passive"))
    )
    (net (code "110") (name "XTAL1") (class "Default")
      (node (ref "IC3") (pin "34") (pinfunction "XTAL1_34") (pintype "input"))
      (node (ref "R1") (pin "1") (pinfunction "1_1") (pintype "passive"))
      (node (ref "Y1") (pin "3") (pinfunction "3_3") (pintype "passive"))
    )
    (net (code "111") (name "XTAL2") (class "Default")
      (node (ref "IC3") (pin "33") (pinfunction "XTAL2_33") (pintype "output"))
      (node (ref "R1") (pin "2") (pinfunction "2_2") (pintype "passive"))
      (node (ref "Y1") (pin "1") (pinfunction "1_1") (pintype "passive"))
    )
    (net (code "112") (name "XVCC") (class "Default")
      (node (ref "F1") (pin "2") (pinfunction "2_2") (pintype "passive"))
      (node (ref "X2") (pin "1") (pinfunction "1_1") (pintype "bidirectional"))
    )
    (net (code "113") (name "unconnected-(IC3-(CLKO{slash}ICP3{slash}INT7)PE7-Pad9)") (class "Default")
      (node (ref "IC3") (pin "9") (pinfunction "(CLKO/ICP3/INT7)PE7_9") (pintype "bidirectional"))
    )
    (net (code "114") (name "unconnected-(IC3-(ICP1)PD4-Pad47)") (class "Default")
      (node (ref "IC3") (pin "47") (pinfunction "(ICP1)PD4_47") (pintype "bidirectional"))
    )
    (net (code "115") (name "unconnected-(IC3-(T1)PD6-Pad49)") (class "Default")
      (node (ref "IC3") (pin "49") (pinfunction "(T1)PD6_49") (pintype "bidirectional"))
    )
    (net (code "116") (name "unconnected-(IC3-(T3{slash}INT6)PE6-Pad8)") (class "Default")
      (node (ref "IC3") (pin "8") (pinfunction "(T3/INT6)PE6_8") (pintype "bidirectional"))
    )
    (net (code "117") (name "unconnected-(IC3-(TOSC1)PG4-Pad29)") (class "Default")
      (node (ref "IC3") (pin "29") (pinfunction "(TOSC1)PG4_29") (pintype "bidirectional"))
    )
    (net (code "118") (name "unconnected-(IC3-(TOSC2)PG3-Pad28)") (class "Default")
      (node (ref "IC3") (pin "28") (pinfunction "(TOSC2)PG3_28") (pintype "bidirectional"))
    )
    (net (code "119") (name "unconnected-(IC3-(XCK0{slash}AIN0)PE2-Pad4)") (class "Default")
      (node (ref "IC3") (pin "4") (pinfunction "(XCK0/AIN0)PE2_4") (pintype "bidirectional"))
    )
    (net (code "120") (name "unconnected-(IC3-(XCK1)PD5-Pad48)") (class "Default")
      (node (ref "IC3") (pin "48") (pinfunction "(XCK1)PD5_48") (pintype "bidirectional"))
    )
    (net (code "121") (name "unconnected-(IC3-PH2(XCK2)-Pad14)") (class "Default")
      (node (ref "IC3") (pin "14") (pinfunction "PH2(XCK2)_14") (pintype "bidirectional"))
    )
    (net (code "122") (name "unconnected-(IC3-PH7(T4)-Pad27)") (class "Default")
      (node (ref "IC3") (pin "27") (pinfunction "PH7(T4)_27") (pintype "bidirectional"))
    )
    (net (code "123") (name "unconnected-(IC3-PJ2(XCK3{slash}PCINT11)-Pad65)") (class "Default")
      (node (ref "IC3") (pin "65") (pinfunction "PJ2(XCK3/PCINT11)_65") (pintype "bidirectional"))
    )
    (net (code "124") (name "unconnected-(IC3-PJ3(PCINT12)-Pad66)") (class "Default")
      (node (ref "IC3") (pin "66") (pinfunction "PJ3(PCINT12)_66") (pintype "bidirectional"))
    )
    (net (code "125") (name "unconnected-(IC3-PJ4(PCINT13)-Pad67)") (class "Default")
      (node (ref "IC3") (pin "67") (pinfunction "PJ4(PCINT13)_67") (pintype "bidirectional"))
    )
    (net (code "126") (name "unconnected-(IC3-PJ5(PCINT14)-Pad68)") (class "Default")
      (node (ref "IC3") (pin "68") (pinfunction "PJ5(PCINT14)_68") (pintype "bidirectional"))
    )
    (net (code "127") (name "unconnected-(IC3-PJ6(PCINT15)-Pad69)") (class "Default")
      (node (ref "IC3") (pin "69") (pinfunction "PJ6(PCINT15)_69") (pintype "bidirectional"))
    )
    (net (code "128") (name "unconnected-(IC3-PJ7-Pad79)") (class "Default")
      (node (ref "IC3") (pin "79") (pinfunction "PJ7_79") (pintype "bidirectional"))
    )
    (net (code "129") (name "unconnected-(IC4-(AIN0{slash}INT1)PD1-Pad7)") (class "Default")
      (node (ref "IC4") (pin "7") (pinfunction "(AIN0/INT1)PD1_7") (pintype "bidirectional"))
    )
    (net (code "130") (name "unconnected-(IC4-(AIN2{slash}PCINT11)PC2-Pad5)") (class "Default")
      (node (ref "IC4") (pin "5") (pinfunction "(AIN2/PCINT11)PC2_5") (pintype "bidirectional"))
    )
    (net (code "131") (name "unconnected-(IC4-(INT4{slash}ICP1{slash}CLK0)PC7-Pad22)") (class "Default")
      (node (ref "IC4") (pin "22") (pinfunction "(INT4/ICP1/CLK0)PC7_22") (pintype "bidirectional"))
    )
    (net (code "132") (name "unconnected-(IC4-(OC0B{slash}INT0)PD0-Pad6)") (class "Default")
      (node (ref "IC4") (pin "6") (pinfunction "(OC0B/INT0)PD0_6") (pintype "bidirectional"))
    )
    (net (code "133") (name "unconnected-(IC4-(OC1A{slash}PCINT8)PC6-Pad23)") (class "Default")
      (node (ref "IC4") (pin "23") (pinfunction "(OC1A/PCINT8)PC6_23") (pintype "bidirectional"))
    )
    (net (code "134") (name "unconnected-(IC4-(PCINT9{slash}OC1B)PC5-Pad25)") (class "Default")
      (node (ref "IC4") (pin "25") (pinfunction "(PCINT9/OC1B)PC5_25") (pintype "bidirectional"))
    )
    (net (code "135") (name "unconnected-(IC4-(PCINT10)PC4-Pad26)") (class "Default")
      (node (ref "IC4") (pin "26") (pinfunction "(PCINT10)PC4_26") (pintype "bidirectional"))
    )
    (net (code "136") (name "unconnected-(IC4-(RTS{slash}AIN5{slash}INT6)PD6-Pad12)") (class "Default")
      (node (ref "IC4") (pin "12") (pinfunction "(RTS/AIN5/INT6)PD6_12") (pintype "bidirectional"))
    )
    (net (code "137") (name "unconnected-(IC4-(SS{slash}PCINT0)PB0-Pad14)") (class "Default")
      (node (ref "IC4") (pin "14") (pinfunction "(SS/PCINT0)PB0_14") (pintype "bidirectional"))
    )
    (net (code "138") (name "unconnected-(IC6-NC{slash}FB-Pad4)") (class "Default")
      (node (ref "IC6") (pin "4") (pinfunction "NC/FB_4") (pintype "passive"))
    )
    (net (code "139") (name "unconnected-(POWER-Pad1)") (class "Default")
      (node (ref "POWER") (pin "1") (pinfunction "1_1") (pintype "passive"))
    )
    (net (code "140") (name "unconnected-(RN1-Pad1)") (class "Default")
      (node (ref "RN1") (pin "1") (pinfunction "1_1") (pintype "passive"))
    )
    (net (code "141") (name "unconnected-(RN1A-2-Pad8)") (class "Default")
      (node (ref "RN1") (pin "8") (pinfunction "2_8") (pintype "passive"))
    )
    (net (code "142") (name "unconnected-(RN1D-1-Pad4)") (class "Default")
      (node (ref "RN1") (pin "4") (pinfunction "1_4") (pintype "passive"))
    )
    (net (code "143") (name "unconnected-(RN1D-2-Pad5)") (class "Default")
      (node (ref "RN1") (pin "5") (pinfunction "2_5") (pintype "passive"))
    )
    (net (code "144") (name "unconnected-(RN2B-1-Pad2)") (class "Default")
      (node (ref "RN2") (pin "2") (pinfunction "1_2") (pintype "passive"))
    )
    (net (code "145") (name "unconnected-(RN2B-2-Pad7)") (class "Default")
      (node (ref "RN2") (pin "7") (pinfunction "2_7") (pintype "passive"))
    )
    (net (code "146") (name "unconnected-(RN2C-1-Pad3)") (class "Default")
      (node (ref "RN2") (pin "3") (pinfunction "1_3") (pintype "passive"))
    )
    (net (code "147") (name "unconnected-(RN2C-2-Pad6)") (class "Default")
      (node (ref "RN2") (pin "6") (pinfunction "2_6") (pintype "passive"))
    )
    (net (code "148") (name "unconnected-(RN3-Pad1)") (class "Default")
      (node (ref "RN3") (pin "1") (pinfunction "1_1") (pintype "passive"))
    )
    (net (code "149") (name "unconnected-(RN3C-1-Pad3)") (class "Default")
      (node (ref "RN3") (pin "3") (pinfunction "1_3") (pintype "passive"))
    )
    (net (code "150") (name "unconnected-(RN3C-2-Pad6)") (class "Default")
      (node (ref "RN3") (pin "6") (pinfunction "2_6") (pintype "passive"))
    )
    (net (code "151") (name "unconnected-(RN6-Pad1)") (class "Default")
      (node (ref "RN6") (pin "1") (pinfunction "1_1") (pintype "passive"))
    )
    (net (code "152") (name "unconnected-(RN6A-2-Pad8)") (class "Default")
      (node (ref "RN6") (pin "8") (pinfunction "2_8") (pintype "passive"))
    )
    (net (code "153") (name "unconnected-(RN6B-1-Pad2)") (class "Default")
      (node (ref "RN6") (pin "2") (pinfunction "1_2") (pintype "passive"))
    )
    (net (code "154") (name "unconnected-(RN6B-2-Pad7)") (class "Default")
      (node (ref "RN6") (pin "7") (pinfunction "2_7") (pintype "passive"))
    )
    (net (code "155") (name "unconnected-(RN6C-1-Pad3)") (class "Default")
      (node (ref "RN6") (pin "3") (pinfunction "1_3") (pintype "passive"))
    )
    (net (code "156") (name "unconnected-(RN6C-2-Pad6)") (class "Default")
      (node (ref "RN6") (pin "6") (pinfunction "2_6") (pintype "passive"))
    )
    (net (code "157") (name "unconnected-(RN6D-1-Pad4)") (class "Default")
      (node (ref "RN6") (pin "4") (pinfunction "1_4") (pintype "passive"))
    )
    (net (code "158") (name "unconnected-(RN6D-2-Pad5)") (class "Default")
      (node (ref "RN6") (pin "5") (pinfunction "2_5") (pintype "passive"))
    )
  )
)
